# untitled-2.net
KiCad netlist of a schematic drawn in EAGLE
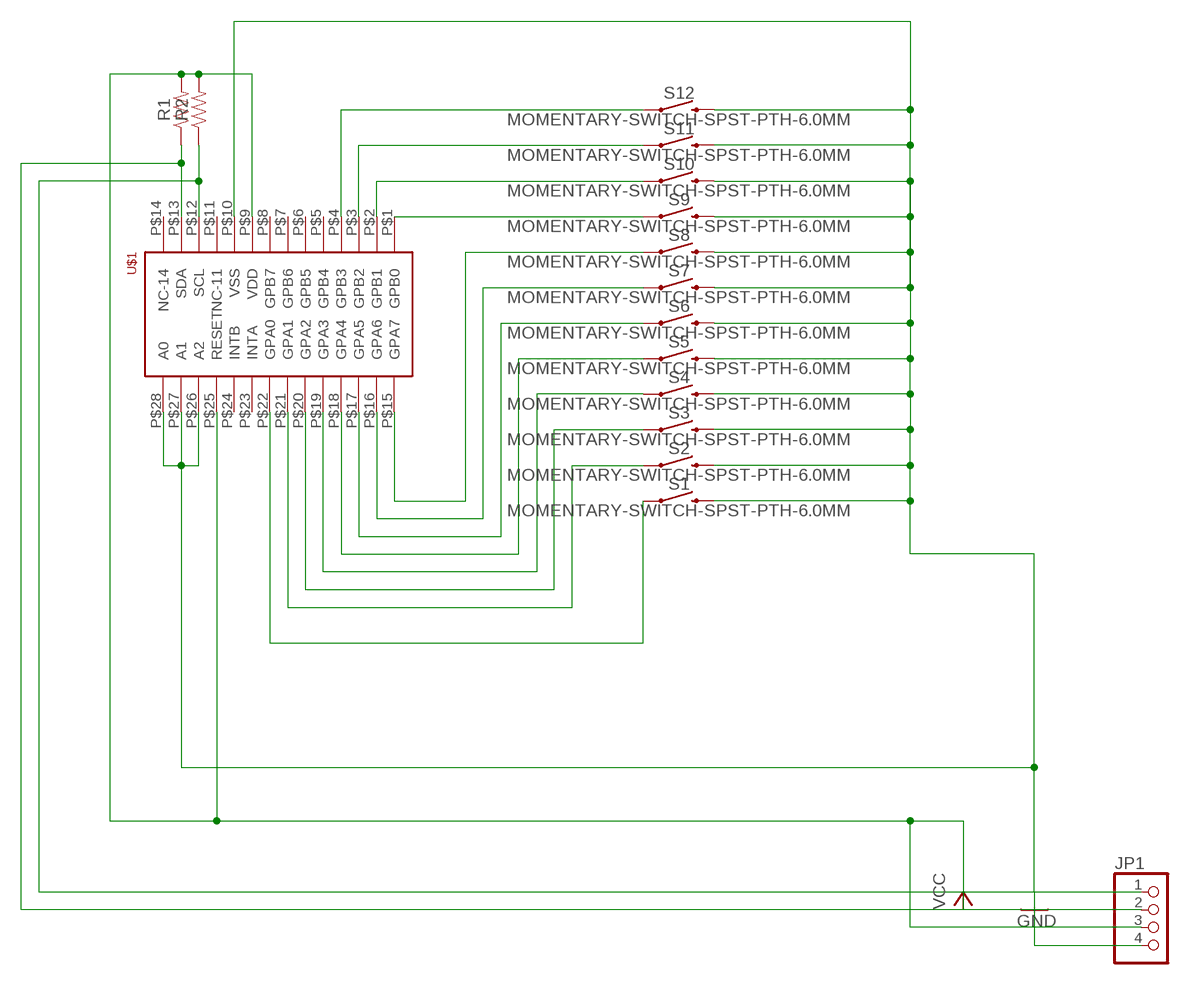
[diagram p0: schematic, sheet 1]

(export (version "E")
  (design (tool "Eeschema 10.0.6"))
  (components
    (comp (ref "JP1")
      (value "PINHD-1X4")
      (footprint "eagle-import:1X04")
      (fields (field (name "SPICEPREFIX") "B"))
      (libsource (lib "eagle-import") (part "PINHD-1X4"))
    )
    (comp (ref "R1")
      (value "RESISTORAXIAL-0.3")
      (footprint "eagle-import:AXIAL-0.3")
      (libsource (lib "eagle-import") (part "RESISTORAXIAL-0.3"))
    )
    (comp (ref "R2")
      (value "RESISTORAXIAL-0.3")
      (footprint "eagle-import:AXIAL-0.3")
      (libsource (lib "eagle-import") (part "RESISTORAXIAL-0.3"))
    )
    (comp (ref "S1")
      (value "MOMENTARY-SWITCH-SPST-PTH-6.0MM")
      (footprint "eagle-import:TACTILE_SWITCH_PTH_6.0MM")
      (libsource (lib "eagle-import") (part "MOMENTARY-SWITCH-SPST-PTH-6.0MM"))
    )
    (comp (ref "S2")
      (value "MOMENTARY-SWITCH-SPST-PTH-6.0MM")
      (footprint "eagle-import:TACTILE_SWITCH_PTH_6.0MM")
      (libsource (lib "eagle-import") (part "MOMENTARY-SWITCH-SPST-PTH-6.0MM"))
    )
    (comp (ref "S3")
      (value "MOMENTARY-SWITCH-SPST-PTH-6.0MM")
      (footprint "eagle-import:TACTILE_SWITCH_PTH_6.0MM")
      (libsource (lib "eagle-import") (part "MOMENTARY-SWITCH-SPST-PTH-6.0MM"))
    )
    (comp (ref "S4")
      (value "MOMENTARY-SWITCH-SPST-PTH-6.0MM")
      (footprint "eagle-import:TACTILE_SWITCH_PTH_6.0MM")
      (libsource (lib "eagle-import") (part "MOMENTARY-SWITCH-SPST-PTH-6.0MM"))
    )
    (comp (ref "S5")
      (value "MOMENTARY-SWITCH-SPST-PTH-6.0MM")
      (footprint "eagle-import:TACTILE_SWITCH_PTH_6.0MM")
      (libsource (lib "eagle-import") (part "MOMENTARY-SWITCH-SPST-PTH-6.0MM"))
    )
    (comp (ref "S6")
      (value "MOMENTARY-SWITCH-SPST-PTH-6.0MM")
      (footprint "eagle-import:TACTILE_SWITCH_PTH_6.0MM")
      (libsource (lib "eagle-import") (part "MOMENTARY-SWITCH-SPST-PTH-6.0MM"))
    )
    (comp (ref "S7")
      (value "MOMENTARY-SWITCH-SPST-PTH-6.0MM")
      (footprint "eagle-import:TACTILE_SWITCH_PTH_6.0MM")
      (libsource (lib "eagle-import") (part "MOMENTARY-SWITCH-SPST-PTH-6.0MM"))
    )
    (comp (ref "S8")
      (value "MOMENTARY-SWITCH-SPST-PTH-6.0MM")
      (footprint "eagle-import:TACTILE_SWITCH_PTH_6.0MM")
      (libsource (lib "eagle-import") (part "MOMENTARY-SWITCH-SPST-PTH-6.0MM"))
    )
    (comp (ref "S9")
      (value "MOMENTARY-SWITCH-SPST-PTH-6.0MM")
      (footprint "eagle-import:TACTILE_SWITCH_PTH_6.0MM")
      (libsource (lib "eagle-import") (part "MOMENTARY-SWITCH-SPST-PTH-6.0MM"))
    )
    (comp (ref "S10")
      (value "MOMENTARY-SWITCH-SPST-PTH-6.0MM")
      (footprint "eagle-import:TACTILE_SWITCH_PTH_6.0MM")
      (libsource (lib "eagle-import") (part "MOMENTARY-SWITCH-SPST-PTH-6.0MM"))
    )
    (comp (ref "S11")
      (value "MOMENTARY-SWITCH-SPST-PTH-6.0MM")
      (footprint "eagle-import:TACTILE_SWITCH_PTH_6.0MM")
      (libsource (lib "eagle-import") (part "MOMENTARY-SWITCH-SPST-PTH-6.0MM"))
    )
    (comp (ref "S12")
      (value "MOMENTARY-SWITCH-SPST-PTH-6.0MM")
      (footprint "eagle-import:TACTILE_SWITCH_PTH_6.0MM")
      (libsource (lib "eagle-import") (part "MOMENTARY-SWITCH-SPST-PTH-6.0MM"))
    )
    (comp (ref "U$1")
      (value "MCP23017-E/SP")
      (footprint "eagle-import:DIP28")
      (libsource (lib "eagle-import") (part "MCP23017-E/SP"))
    )
  )
  (nets
    (net (code "1") (name "GND") (class "Default")
      (node (ref "JP1") (pin "4") (pinfunction "4_4") (pintype "passive"))
      (node (ref "S1") (pin "3") (pinfunction "2_3") (pintype "passive"))
      (node (ref "S10") (pin "3") (pinfunction "2_3") (pintype "passive"))
      (node (ref "S11") (pin "3") (pinfunction "2_3") (pintype "passive"))
      (node (ref "S12") (pin "3") (pinfunction "2_3") (pintype "passive"))
      (node (ref "S2") (pin "3") (pinfunction "2_3") (pintype "passive"))
      (node (ref "S3") (pin "3") (pinfunction "2_3") (pintype "passive"))
      (node (ref "S4") (pin "3") (pinfunction "2_3") (pintype "passive"))
      (node (ref "S5") (pin "3") (pinfunction "2_3") (pintype "passive"))
      (node (ref "S6") (pin "3") (pinfunction "2_3") (pintype "passive"))
      (node (ref "S7") (pin "3") (pinfunction "2_3") (pintype "passive"))
      (node (ref "S8") (pin "3") (pinfunction "2_3") (pintype "passive"))
      (node (ref "S9") (pin "3") (pinfunction "2_3") (pintype "passive"))
      (node (ref "U$1") (pin "P$10") (pinfunction "VSS_P$10") (pintype "bidirectional"))
      (node (ref "U$1") (pin "P$26") (pinfunction "A2_P$26") (pintype "bidirectional"))
      (node (ref "U$1") (pin "P$27") (pinfunction "A1_P$27") (pintype "bidirectional"))
      (node (ref "U$1") (pin "P$28") (pinfunction "A0_P$28") (pintype "bidirectional"))
    )
    (net (code "2") (name "Net-(R1-1)") (class "Default")
      (node (ref "JP1") (pin "2") (pinfunction "2_2") (pintype "passive"))
      (node (ref "R1") (pin "P$1") (pinfunction "1_P$1") (pintype "passive"))
      (node (ref "U$1") (pin "P$13") (pinfunction "SDA_P$13") (pintype "bidirectional"))
    )
    (net (code "3") (name "Net-(R2-1)") (class "Default")
      (node (ref "JP1") (pin "1") (pinfunction "1_1") (pintype "passive"))
      (node (ref "R2") (pin "P$1") (pinfunction "1_P$1") (pintype "passive"))
      (node (ref "U$1") (pin "P$12") (pinfunction "SCL_P$12") (pintype "bidirectional"))
    )
    (net (code "4") (name "Net-(U$1-GPA0)") (class "Default")
      (node (ref "S1") (pin "1") (pinfunction "1_1") (pintype "passive"))
      (node (ref "U$1") (pin "P$22") (pinfunction "GPA0_P$22") (pintype "bidirectional"))
    )
    (net (code "5") (name "Net-(U$1-GPA1)") (class "Default")
      (node (ref "S2") (pin "1") (pinfunction "1_1") (pintype "passive"))
      (node (ref "U$1") (pin "P$21") (pinfunction "GPA1_P$21") (pintype "bidirectional"))
    )
    (net (code "6") (name "Net-(U$1-GPA2)") (class "Default")
      (node (ref "S3") (pin "1") (pinfunction "1_1") (pintype "passive"))
      (node (ref "U$1") (pin "P$20") (pinfunction "GPA2_P$20") (pintype "bidirectional"))
    )
    (net (code "7") (name "Net-(U$1-GPA3)") (class "Default")
      (node (ref "S4") (pin "1") (pinfunction "1_1") (pintype "passive"))
      (node (ref "U$1") (pin "P$19") (pinfunction "GPA3_P$19") (pintype "bidirectional"))
    )
    (net (code "8") (name "Net-(U$1-GPA4)") (class "Default")
      (node (ref "S5") (pin "1") (pinfunction "1_1") (pintype "passive"))
      (node (ref "U$1") (pin "P$18") (pinfunction "GPA4_P$18") (pintype "bidirectional"))
    )
    (net (code "9") (name "Net-(U$1-GPA5)") (class "Default")
      (node (ref "S6") (pin "1") (pinfunction "1_1") (pintype "passive"))
      (node (ref "U$1") (pin "P$17") (pinfunction "GPA5_P$17") (pintype "bidirectional"))
    )
    (net (code "10") (name "Net-(U$1-GPA6)") (class "Default")
      (node (ref "S7") (pin "1") (pinfunction "1_1") (pintype "passive"))
      (node (ref "U$1") (pin "P$16") (pinfunction "GPA6_P$16") (pintype "bidirectional"))
    )
    (net (code "11") (name "Net-(U$1-GPA7)") (class "Default")
      (node (ref "S8") (pin "1") (pinfunction "1_1") (pintype "passive"))
      (node (ref "U$1") (pin "P$15") (pinfunction "GPA7_P$15") (pintype "bidirectional"))
    )
    (net (code "12") (name "Net-(U$1-GPB0)") (class "Default")
      (node (ref "S9") (pin "1") (pinfunction "1_1") (pintype "passive"))
      (node (ref "U$1") (pin "P$1") (pinfunction "GPB0_P$1") (pintype "bidirectional"))
    )
    (net (code "13") (name "Net-(U$1-GPB1)") (class "Default")
      (node (ref "S10") (pin "1") (pinfunction "1_1") (pintype "passive"))
      (node (ref "U$1") (pin "P$2") (pinfunction "GPB1_P$2") (pintype "bidirectional"))
    )
    (net (code "14") (name "Net-(U$1-GPB2)") (class "Default")
      (node (ref "S11") (pin "1") (pinfunction "1_1") (pintype "passive"))
      (node (ref "U$1") (pin "P$3") (pinfunction "GPB2_P$3") (pintype "bidirectional"))
    )
    (net (code "15") (name "Net-(U$1-GPB3)") (class "Default")
      (node (ref "S12") (pin "1") (pinfunction "1_1") (pintype "passive"))
      (node (ref "U$1") (pin "P$4") (pinfunction "GPB3_P$4") (pintype "bidirectional"))
    )
    (net (code "16") (name "VCC") (class "Default")
      (node (ref "JP1") (pin "3") (pinfunction "3_3") (pintype "passive"))
      (node (ref "R1") (pin "P$2") (pinfunction "2_P$2") (pintype "passive"))
      (node (ref "R2") (pin "P$2") (pinfunction "2_P$2") (pintype "passive"))
      (node (ref "U$1") (pin "P$25") (pinfunction "RESET_P$25") (pintype "bidirectional"))
      (node (ref "U$1") (pin "P$9") (pinfunction "VDD_P$9") (pintype "bidirectional"))
    )
    (net (code "17") (name "unconnected-(U$1-GPB4-PadP$5)") (class "Default")
      (node (ref "U$1") (pin "P$5") (pinfunction "GPB4_P$5") (pintype "bidirectional"))
    )
    (net (code "18") (name "unconnected-(U$1-GPB5-PadP$6)") (class "Default")
      (node (ref "U$1") (pin "P$6") (pinfunction "GPB5_P$6") (pintype "bidirectional"))
    )
    (net (code "19") (name "unconnected-(U$1-GPB6-PadP$7)") (class "Default")
      (node (ref "U$1") (pin "P$7") (pinfunction "GPB6_P$7") (pintype "bidirectional"))
    )
    (net (code "20") (name "unconnected-(U$1-GPB7-PadP$8)") (class "Default")
      (node (ref "U$1") (pin "P$8") (pinfunction "GPB7_P$8") (pintype "bidirectional"))
    )
    (net (code "21") (name "unconnected-(U$1-INTA-PadP$23)") (class "Default")
      (node (ref "U$1") (pin "P$23") (pinfunction "INTA_P$23") (pintype "bidirectional"))
    )
    (net (code "22") (name "unconnected-(U$1-INTB-PadP$24)") (class "Default")
      (node (ref "U$1") (pin "P$24") (pinfunction "INTB_P$24") (pintype "bidirectional"))
    )
    (net (code "23") (name "unconnected-(U$1-NC-11-PadP$11)") (class "Default")
      (node (ref "U$1") (pin "P$11") (pinfunction "NC-11_P$11") (pintype "bidirectional"))
    )
    (net (code "24") (name "unconnected-(U$1-NC-14-PadP$14)") (class "Default")
      (node (ref "U$1") (pin "P$14") (pinfunction "NC-14_P$14") (pintype "bidirectional"))
    )
  )
)
